# AD835_Mixer.net
KiCad netlist of a schematic drawn in Altium Designer
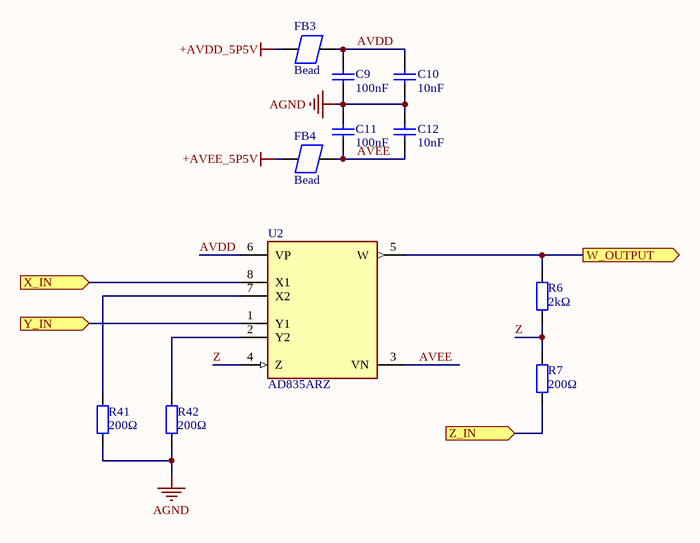
[diagram p0: AD835_Mixer.SchDoc]

(export (version "E")
  (design (tool "Eeschema 10.0.6"))
  (components
    (comp (ref "C9")
      (value "100nF")
      (footprint "0603_C")
      (description "贴片电容")
      (libsource (lib "Miscellaneous Devices LC") (part "0603 100nF (104) 10% 50V"))
    )
    (comp (ref "C10")
      (value "10nF")
      (footprint "0603_C")
      (description "贴片电容")
      (libsource (lib "Miscellaneous Devices LC") (part "0603 10nF (103) 10% 50V"))
    )
    (comp (ref "C11")
      (value "100nF")
      (footprint "0603_C")
      (description "贴片电容")
      (libsource (lib "Miscellaneous Devices LC") (part "0603 100nF (104) 10% 50V"))
    )
    (comp (ref "C12")
      (value "10nF")
      (footprint "0603_C")
      (description "贴片电容")
      (libsource (lib "Miscellaneous Devices LC") (part "0603 10nF (103) 10% 50V"))
    )
    (comp (ref "FB3") (value "Bead") (footprint "0805_L") (libsource (lib "OlvkLib") (part "Bead")))
    (comp (ref "FB4") (value "Bead") (footprint "0805_L") (libsource (lib "OlvkLib") (part "Bead")))
    (comp (ref "R6")
      (value "2kΩ")
      (footprint "0603_R")
      (description "贴片电阻")
      (libsource (lib "Miscellaneous Devices LC") (part "0603 2KΩ (2001) 1%"))
    )
    (comp (ref "R7")
      (value "200Ω")
      (footprint "0603_R")
      (description "贴片电阻")
      (libsource (lib "Miscellaneous Devices LC") (part "0603 200Ω (2000) 1%"))
    )
    (comp (ref "R41")
      (value "200Ω")
      (footprint "0603_R")
      (description "贴片电阻")
      (libsource (lib "Miscellaneous Devices LC") (part "0603 200Ω (2000) 1%"))
    )
    (comp (ref "R42")
      (value "200Ω")
      (footprint "0603_R")
      (description "贴片电阻")
      (libsource (lib "Miscellaneous Devices LC") (part "0603 200Ω (2000) 1%"))
    )
    (comp (ref "U2")
      (value "AD835ARZ")
      (footprint "FP-R-8-IPC_A")
      (description "ANALOG MULTIPLIER OR DIVIDER, 25")
      (libsource (lib "Altium Content Vault") (part "636e6c1bcac4b79735226ad9f2367f8"))
    )
  )
  (nets
    (net (code "1") (name "+AVDD_5P5V") (class "Default")
      (node (ref "FB3") (pin "1") (pinfunction "1_1") (pintype "passive"))
    )
    (net (code "2") (name "+AVEE_5P5V") (class "Default")
      (node (ref "FB4") (pin "1") (pinfunction "1_1") (pintype "passive"))
    )
    (net (code "3") (name "/AVDD") (class "Default")
      (node (ref "C10") (pin "2") (pinfunction "2_2") (pintype "passive"))
      (node (ref "C9") (pin "2") (pinfunction "2_2") (pintype "passive"))
      (node (ref "FB3") (pin "2") (pinfunction "2_2") (pintype "passive"))
      (node (ref "U2") (pin "6") (pinfunction "VP_6") (pintype "power_in"))
    )
    (net (code "4") (name "/AVEE") (class "Default")
      (node (ref "C11") (pin "2") (pinfunction "2_2") (pintype "passive"))
      (node (ref "C12") (pin "2") (pinfunction "2_2") (pintype "passive"))
      (node (ref "FB4") (pin "2") (pinfunction "2_2") (pintype "passive"))
      (node (ref "U2") (pin "3") (pinfunction "VN_3") (pintype "power_in"))
    )
    (net (code "5") (name "/W_OUTPUT") (class "Default")
      (node (ref "R6") (pin "2") (pinfunction "2_2") (pintype "passive"))
      (node (ref "U2") (pin "5") (pinfunction "W_5") (pintype "output"))
    )
    (net (code "6") (name "/X_IN") (class "Default")
      (node (ref "U2") (pin "8") (pinfunction "X1_8") (pintype "tri_state"))
    )
    (net (code "7") (name "/Y_IN") (class "Default")
      (node (ref "U2") (pin "1") (pinfunction "Y1_1") (pintype "tri_state"))
    )
    (net (code "8") (name "/Z") (class "Default")
      (node (ref "R6") (pin "1") (pinfunction "1_1") (pintype "passive"))
      (node (ref "R7") (pin "2") (pinfunction "2_2") (pintype "passive"))
      (node (ref "U2") (pin "4") (pinfunction "Z_4") (pintype "input"))
    )
    (net (code "9") (name "/Z_IN") (class "Default")
      (node (ref "R7") (pin "1") (pinfunction "1_1") (pintype "passive"))
    )
    (net (code "10") (name "AGND") (class "Default")
      (node (ref "C10") (pin "1") (pinfunction "1_1") (pintype "passive"))
      (node (ref "C11") (pin "1") (pinfunction "1_1") (pintype "passive"))
      (node (ref "C12") (pin "1") (pinfunction "1_1") (pintype "passive"))
      (node (ref "C9") (pin "1") (pinfunction "1_1") (pintype "passive"))
      (node (ref "R41") (pin "1") (pinfunction "1_1") (pintype "passive"))
      (node (ref "R42") (pin "1") (pinfunction "1_1") (pintype "passive"))
    )
    (net (code "11") (name "Net-(U2-X2)") (class "Default")
      (node (ref "R41") (pin "2") (pinfunction "2_2") (pintype "passive"))
      (node (ref "U2") (pin "7") (pinfunction "X2_7") (pintype "tri_state"))
    )
    (net (code "12") (name "Net-(U2-Y2)") (class "Default")
      (node (ref "R42") (pin "2") (pinfunction "2_2") (pintype "passive"))
      (node (ref "U2") (pin "2") (pinfunction "Y2_2") (pintype "tri_state"))
    )
  )
)
